# 2228_Emetteur_Alimentation.net
KiCad netlist of a schematic drawn in Altium Designer
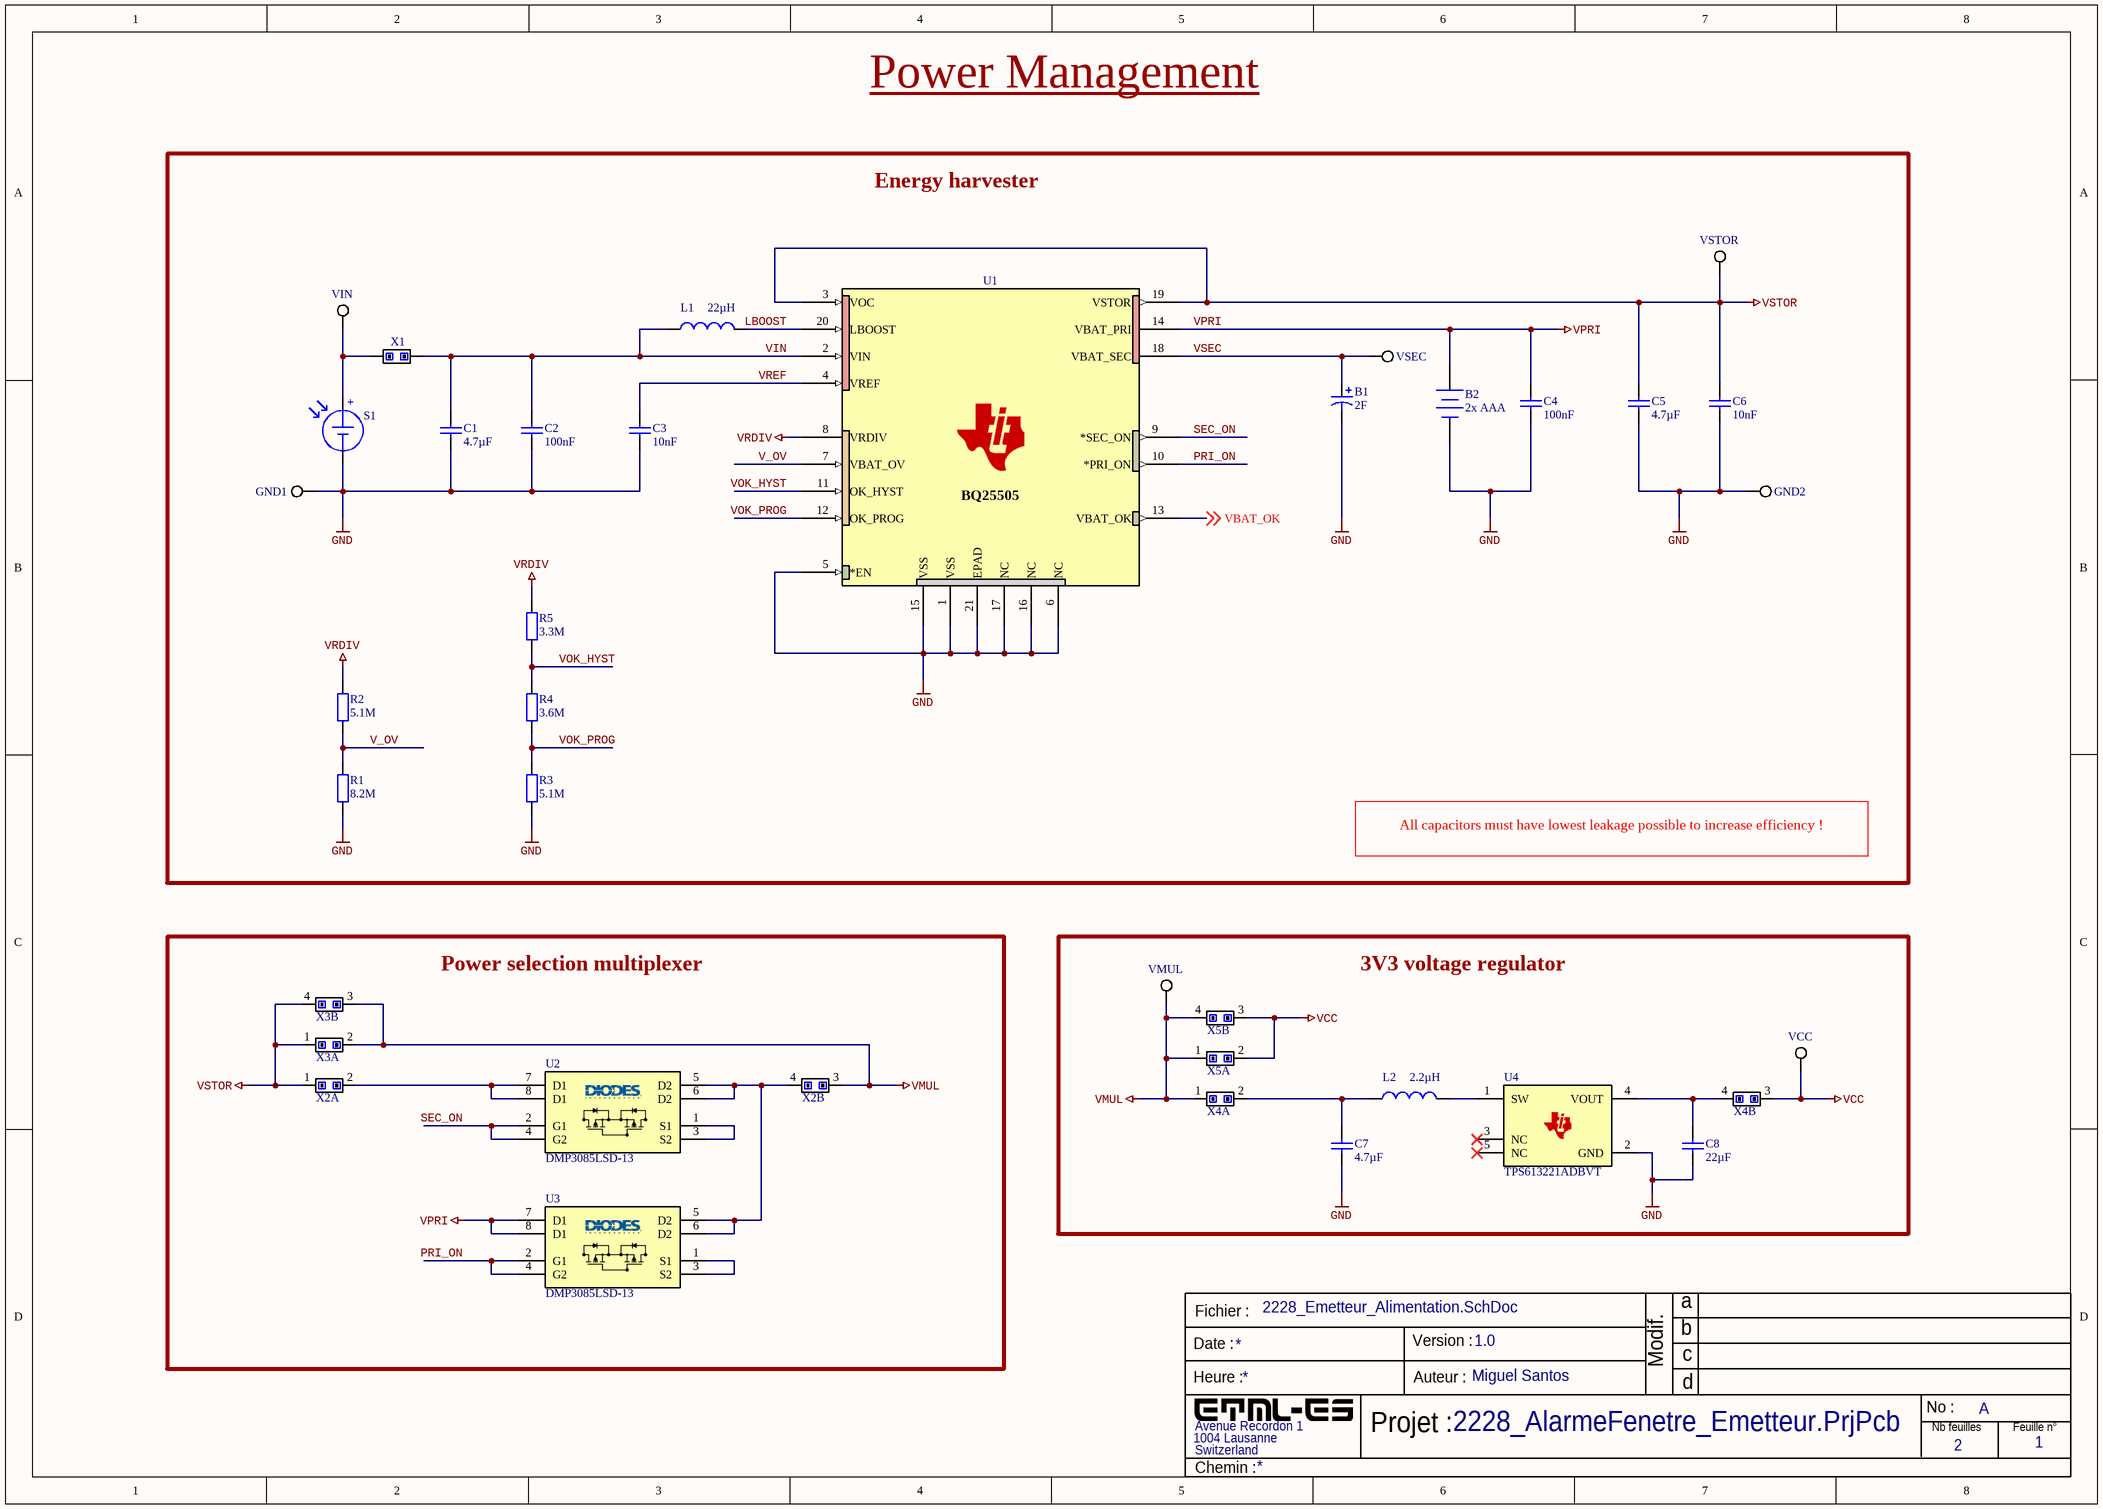
[diagram p0: 2228_Emetteur_Alimentation.SchDoc]

(export (version "E")
  (design (tool "Eeschema 10.0.6"))
  (components
    (comp (ref "B1")
      (value "2F")
      (footprint "2228_AlarmeFenetre_Footprints:SuperCap")
      (description "Polarized SuperCapacitor (Radial)")
      (fields (field (name "Comment") "SUPERCAP"))
      (libsource (lib "2228_AlarmeFenetre_Symbols") (part "SUPERCAP"))
    )
    (comp (ref "B2")
      (value "2x AAA")
      (footprint "WE_2PINS")
      (description "Multicell Battery")
      (libsource (lib "2228_AlarmeFenetre_Symbols") (part "Battery"))
    )
    (comp (ref "C1")
      (value "4.7µF")
      (footprint "CAP_0805")
      (description "Capacitor")
      (fields (field (name "Comment") "CAP_SMD"))
      (libsource (lib "2228_AlarmeFenetre_Symbols") (part "CAP_SMD"))
    )
    (comp (ref "C2")
      (value "100nF")
      (footprint "CAP_0805")
      (description "Capacitor")
      (fields (field (name "Comment") "CAP_SMD"))
      (libsource (lib "2228_AlarmeFenetre_Symbols") (part "CAP_SMD"))
    )
    (comp (ref "C3")
      (value "10nF")
      (footprint "CAP_0805")
      (description "Capacitor")
      (fields (field (name "Comment") "CAP_SMD"))
      (libsource (lib "2228_AlarmeFenetre_Symbols") (part "CAP_SMD"))
    )
    (comp (ref "C4")
      (value "100nF")
      (footprint "CAP_0805")
      (description "Capacitor")
      (fields (field (name "Comment") "CAP_SMD"))
      (libsource (lib "2228_AlarmeFenetre_Symbols") (part "CAP_SMD"))
    )
    (comp (ref "C5")
      (value "4.7µF")
      (footprint "CAP_0805")
      (description "Capacitor")
      (fields (field (name "Comment") "CAP_SMD"))
      (libsource (lib "2228_AlarmeFenetre_Symbols") (part "CAP_SMD"))
    )
    (comp (ref "C6")
      (value "10nF")
      (footprint "CAP_0805")
      (description "Capacitor")
      (fields (field (name "Comment") "CAP_SMD"))
      (libsource (lib "2228_AlarmeFenetre_Symbols") (part "CAP_SMD"))
    )
    (comp (ref "C7")
      (value "4.7µF")
      (footprint "CAP_0805")
      (description "Capacitor")
      (fields (field (name "Comment") "CAP_SMD"))
      (libsource (lib "2228_AlarmeFenetre_Symbols") (part "CAP_SMD"))
    )
    (comp (ref "C8")
      (value "22µF")
      (footprint "CAP_0805")
      (description "Capacitor")
      (fields (field (name "Comment") "CAP_SMD"))
      (libsource (lib "2228_AlarmeFenetre_Symbols") (part "CAP_SMD"))
    )
    (comp (ref "GND1")
      (value "5019")
      (footprint "KSTN-5019_V")
      (description "Test Point, 1 Position SMD, RoHS, Tape and Reel")
      (libsource (lib "Altium Content Vault") (part "TESTPOINT_WHITE"))
    )
    (comp (ref "GND2")
      (value "5019")
      (footprint "KSTN-5019_V")
      (description "Test Point, 1 Position SMD, RoHS, Tape and Reel")
      (libsource (lib "Altium Content Vault") (part "TESTPOINT_WHITE"))
    )
    (comp (ref "L1")
      (value "22µH")
      (footprint "WE-LQFS_4828")
      (description "Inductor SMD")
      (fields (field (name "Comment") "IND_SMD"))
      (libsource (lib "2228_AlarmeFenetre_Symbols") (part "IND_SMD"))
    )
    (comp (ref "L2")
      (value "2.2µH")
      (footprint "IND_0805")
      (description "Inductor SMD")
      (fields (field (name "Comment") "IND_SMD"))
      (libsource (lib "2228_AlarmeFenetre_Symbols") (part "IND_SMD"))
    )
    (comp (ref "R1")
      (value "8.2M")
      (footprint "RES_0805")
      (fields (field (name "Comment") "RES_SMD"))
      (libsource (lib "2228_AlarmeFenetre_Symbols") (part "RES_SMD"))
    )
    (comp (ref "R2")
      (value "5.1M")
      (footprint "RES_0805")
      (fields (field (name "Comment") "RES_SMD"))
      (libsource (lib "2228_AlarmeFenetre_Symbols") (part "RES_SMD"))
    )
    (comp (ref "R3")
      (value "5.1M")
      (footprint "RES_0805")
      (fields (field (name "Comment") "RES_SMD"))
      (libsource (lib "2228_AlarmeFenetre_Symbols") (part "RES_SMD"))
    )
    (comp (ref "R4")
      (value "3.6M")
      (footprint "RES_0805")
      (fields (field (name "Comment") "RES_SMD"))
      (libsource (lib "2228_AlarmeFenetre_Symbols") (part "RES_SMD"))
    )
    (comp (ref "R5")
      (value "3.3M")
      (footprint "RES_0805")
      (fields (field (name "Comment") "RES_SMD"))
      (libsource (lib "2228_AlarmeFenetre_Symbols") (part "RES_SMD"))
    )
    (comp (ref "S1")
      (value "Solar_Cell")
      (footprint "KXOB25-05X3F-TR")
      (description "Anysolar KXOB25-05X3F")
      (fields (field (name "MANUFACTURER") "Anysolar"))
      (libsource (lib "2228_AlarmeFenetre_Symbols") (part "Solar_Cell"))
    )
    (comp (ref "U1")
      (value "BQ25505")
      (footprint "2228_AlarmeFenetre_Footprints:QFN_25505")
      (description "Low power energy harvester")
      (fields (field (name "MANUFACTURER") "Texas Instruments"))
      (libsource (lib "2228_AlarmeFenetre_Symbols") (part "BQ25505RGRR"))
    )
    (comp (ref "U2")
      (value "DMP3085LSD-13")
      (footprint "2228_AlarmeFenetre_Footprints:SO-8")
      (fields (field (name "MANUFACTURER") "Diodes Inc"))
      (libsource (lib "2228_AlarmeFenetre_Symbols") (part "DMP3085LSD-13"))
    )
    (comp (ref "U3")
      (value "DMP3085LSD-13")
      (footprint "2228_AlarmeFenetre_Footprints:SO-8")
      (fields (field (name "MANUFACTURER") "Diodes Inc"))
      (libsource (lib "2228_AlarmeFenetre_Symbols") (part "DMP3085LSD-13"))
    )
    (comp (ref "U4")
      (value "TPS613221ADBVT")
      (footprint "2228_AlarmeFenetre_Footprints:SOT95P280X145-5N")
      (fields (field (name "MANUFACTURER") "Texas Instruments"))
      (libsource (lib "2228_AlarmeFenetre_Symbols") (part "TPS613221ADBVT"))
    )
    (comp (ref "VCC")
      (value "5019")
      (footprint "KSTN-5019_V")
      (description "Test Point, 1 Position SMD, RoHS, Tape and Reel")
      (libsource (lib "Altium Content Vault") (part "TESTPOINT_WHITE"))
    )
    (comp (ref "VIN")
      (value "5019")
      (footprint "KSTN-5019_V")
      (description "Test Point, 1 Position SMD, RoHS, Tape and Reel")
      (libsource (lib "Altium Content Vault") (part "TESTPOINT_WHITE"))
    )
    (comp (ref "VMUL")
      (value "5019")
      (footprint "KSTN-5019_V")
      (description "Test Point, 1 Position SMD, RoHS, Tape and Reel")
      (libsource (lib "Altium Content Vault") (part "TESTPOINT_WHITE"))
    )
    (comp (ref "VSEC")
      (value "5019")
      (footprint "KSTN-5019_V")
      (description "Test Point, 1 Position SMD, RoHS, Tape and Reel")
      (libsource (lib "Altium Content Vault") (part "TESTPOINT_WHITE"))
    )
    (comp (ref "VSTOR")
      (value "5019")
      (footprint "KSTN-5019_V")
      (description "Test Point, 1 Position SMD, RoHS, Tape and Reel")
      (libsource (lib "Altium Content Vault") (part "TESTPOINT_WHITE"))
    )
    (comp (ref "X1")
      (value "2PIN_HEADER")
      (footprint "HEADER_2PINS")
      (libsource (lib "2228_AlarmeFenetre_Symbols") (part "2PIN_HEADER"))
    )
    (comp (ref "X2")
      (value "2X2PIN_HEADER")
      (footprint "2x2_HEADER")
      (libsource (lib "2228_AlarmeFenetre_Symbols") (part "2X2PIN_HEADER"))
    )
    (comp (ref "X3")
      (value "2X2PIN_HEADER")
      (footprint "2x2_HEADER")
      (libsource (lib "") (part "2X2PIN_HEADER_1"))
    )
    (comp (ref "X4")
      (value "2X2PIN_HEADER")
      (footprint "2x2_HEADER")
      (libsource (lib "") (part "2X2PIN_HEADER_1"))
    )
    (comp (ref "X5")
      (value "2X2PIN_HEADER")
      (footprint "2x2_HEADER")
      (libsource (lib "") (part "2X2PIN_HEADER_1"))
    )
  )
  (nets
    (net (code "1") (name "/LBOOST") (class "Default")
      (node (ref "L1") (pin "2") (pinfunction "2_2") (pintype "passive"))
      (node (ref "U1") (pin "20") (pinfunction "LBOOST_20") (pintype "input"))
    )
    (net (code "2") (name "/PRI_ON") (class "Default")
      (node (ref "U1") (pin "10") (pinfunction "*PRI_ON_10") (pintype "output"))
      (node (ref "U3") (pin "2") (pinfunction "G1_2") (pintype "passive"))
      (node (ref "U3") (pin "4") (pinfunction "G2_4") (pintype "passive"))
    )
    (net (code "3") (name "/SEC_ON") (class "Default")
      (node (ref "U1") (pin "9") (pinfunction "*SEC_ON_9") (pintype "output"))
      (node (ref "U2") (pin "2") (pinfunction "G1_2") (pintype "passive"))
      (node (ref "U2") (pin "4") (pinfunction "G2_4") (pintype "passive"))
    )
    (net (code "4") (name "/VIN") (class "Default")
      (node (ref "C1") (pin "2") (pinfunction "2_2") (pintype "passive"))
      (node (ref "C2") (pin "2") (pinfunction "2_2") (pintype "passive"))
      (node (ref "L1") (pin "1") (pinfunction "1_1") (pintype "passive"))
      (node (ref "U1") (pin "2") (pinfunction "VIN_2") (pintype "input"))
      (node (ref "X1") (pin "2") (pinfunction "2_2") (pintype "passive"))
    )
    (net (code "5") (name "/VOK_HYST") (class "Default")
      (node (ref "R4") (pin "1") (pinfunction "1_1") (pintype "passive"))
      (node (ref "R5") (pin "2") (pinfunction "2_2") (pintype "passive"))
      (node (ref "U1") (pin "11") (pinfunction "OK_HYST_11") (pintype "input"))
    )
    (net (code "6") (name "/VOK_PROG") (class "Default")
      (node (ref "R3") (pin "1") (pinfunction "1_1") (pintype "passive"))
      (node (ref "R4") (pin "2") (pinfunction "2_2") (pintype "passive"))
      (node (ref "U1") (pin "12") (pinfunction "OK_PROG_12") (pintype "input"))
    )
    (net (code "7") (name "/VREF") (class "Default")
      (node (ref "C3") (pin "1") (pinfunction "1_1") (pintype "passive"))
      (node (ref "U1") (pin "4") (pinfunction "VREF_4") (pintype "input"))
    )
    (net (code "8") (name "/VSEC") (class "Default")
      (node (ref "B1") (pin "1") (pinfunction "1_1") (pintype "passive"))
      (node (ref "U1") (pin "18") (pinfunction "VBAT_SEC_18") (pintype "power_in"))
      (node (ref "VSEC") (pin "1") (pinfunction "1_1") (pintype "passive"))
    )
    (net (code "9") (name "/V_OV") (class "Default")
      (node (ref "R1") (pin "1") (pinfunction "1_1") (pintype "passive"))
      (node (ref "R2") (pin "2") (pinfunction "2_2") (pintype "passive"))
      (node (ref "U1") (pin "7") (pinfunction "VBAT_OV_7") (pintype "input"))
    )
    (net (code "10") (name "GND") (class "Default")
      (node (ref "B1") (pin "2") (pinfunction "2_2") (pintype "passive"))
      (node (ref "B2") (pin "2") (pinfunction "2_2") (pintype "passive"))
      (node (ref "C1") (pin "1") (pinfunction "1_1") (pintype "passive"))
      (node (ref "C2") (pin "1") (pinfunction "1_1") (pintype "passive"))
      (node (ref "C3") (pin "2") (pinfunction "2_2") (pintype "passive"))
      (node (ref "C4") (pin "1") (pinfunction "1_1") (pintype "passive"))
      (node (ref "C5") (pin "1") (pinfunction "1_1") (pintype "passive"))
      (node (ref "C6") (pin "1") (pinfunction "1_1") (pintype "passive"))
      (node (ref "C7") (pin "1") (pinfunction "1_1") (pintype "passive"))
      (node (ref "C8") (pin "1") (pinfunction "1_1") (pintype "passive"))
      (node (ref "GND1") (pin "1") (pinfunction "1_1") (pintype "passive"))
      (node (ref "GND2") (pin "1") (pinfunction "1_1") (pintype "passive"))
      (node (ref "R1") (pin "2") (pinfunction "2_2") (pintype "passive"))
      (node (ref "R3") (pin "2") (pinfunction "2_2") (pintype "passive"))
      (node (ref "S1") (pin "2") (pinfunction "-_2") (pintype "power_in"))
      (node (ref "U1") (pin "1") (pinfunction "VSS_1") (pintype "power_in"))
      (node (ref "U1") (pin "15") (pinfunction "VSS_15") (pintype "power_in"))
      (node (ref "U1") (pin "16") (pinfunction "NC_16") (pintype "passive"))
      (node (ref "U1") (pin "17") (pinfunction "NC_17") (pintype "passive"))
      (node (ref "U1") (pin "21") (pinfunction "EPAD_21") (pintype "passive"))
      (node (ref "U1") (pin "5") (pinfunction "*EN_5") (pintype "input"))
      (node (ref "U1") (pin "6") (pinfunction "NC_6") (pintype "passive"))
      (node (ref "U4") (pin "2") (pinfunction "GND_2") (pintype "power_in"))
    )
    (net (code "11") (name "Net-(C7-Pad2)") (class "Default")
      (node (ref "C7") (pin "2") (pinfunction "2_2") (pintype "passive"))
      (node (ref "L2") (pin "1") (pinfunction "1_1") (pintype "passive"))
      (node (ref "X4") (pin "2") (pinfunction "2_2") (pintype "passive"))
    )
    (net (code "12") (name "Net-(S1-+)") (class "Default")
      (node (ref "S1") (pin "1") (pinfunction "+_1") (pintype "power_in"))
      (node (ref "VIN") (pin "1") (pinfunction "1_1") (pintype "passive"))
      (node (ref "X1") (pin "1") (pinfunction "1_1") (pintype "passive"))
    )
    (net (code "13") (name "Net-(U2-D1-Pad7)") (class "Default")
      (node (ref "U2") (pin "7") (pinfunction "D1_7") (pintype "passive"))
      (node (ref "U2") (pin "8") (pinfunction "D1_8") (pintype "passive"))
      (node (ref "X2") (pin "2") (pinfunction "2_2") (pintype "passive"))
    )
    (net (code "14") (name "Net-(U2-D2-Pad5)") (class "Default")
      (node (ref "U2") (pin "5") (pinfunction "D2_5") (pintype "passive"))
      (node (ref "U2") (pin "6") (pinfunction "D2_6") (pintype "passive"))
      (node (ref "U3") (pin "5") (pinfunction "D2_5") (pintype "passive"))
      (node (ref "U3") (pin "6") (pinfunction "D2_6") (pintype "passive"))
      (node (ref "X2") (pin "4") (pinfunction "4_4") (pintype "passive"))
    )
    (net (code "15") (name "Net-(U2-S1)") (class "Default")
      (node (ref "U2") (pin "1") (pinfunction "S1_1") (pintype "passive"))
      (node (ref "U2") (pin "3") (pinfunction "S2_3") (pintype "passive"))
    )
    (net (code "16") (name "Net-(U3-S1)") (class "Default")
      (node (ref "U3") (pin "1") (pinfunction "S1_1") (pintype "passive"))
      (node (ref "U3") (pin "3") (pinfunction "S2_3") (pintype "passive"))
    )
    (net (code "17") (name "Net-(U4-SW)") (class "Default")
      (node (ref "L2") (pin "2") (pinfunction "2_2") (pintype "passive"))
      (node (ref "U4") (pin "1") (pinfunction "SW_1") (pintype "power_in"))
    )
    (net (code "18") (name "Net-(U4-VOUT)") (class "Default")
      (node (ref "C8") (pin "2") (pinfunction "2_2") (pintype "passive"))
      (node (ref "U4") (pin "4") (pinfunction "VOUT_4") (pintype "power_in"))
      (node (ref "X4") (pin "4") (pinfunction "4_4") (pintype "passive"))
    )
    (net (code "19") (name "VBAT_OK") (class "Default")
      (node (ref "U1") (pin "13") (pinfunction "VBAT_OK_13") (pintype "output"))
    )
    (net (code "20") (name "VCC") (class "Default")
      (node (ref "VCC") (pin "1") (pinfunction "1_1") (pintype "passive"))
      (node (ref "X4") (pin "3") (pinfunction "3_3") (pintype "passive"))
      (node (ref "X5") (pin "2") (pinfunction "2_2") (pintype "passive"))
      (node (ref "X5") (pin "3") (pinfunction "3_3") (pintype "passive"))
    )
    (net (code "21") (name "VMUL") (class "Default")
      (node (ref "VMUL") (pin "1") (pinfunction "1_1") (pintype "passive"))
      (node (ref "X2") (pin "3") (pinfunction "3_3") (pintype "passive"))
      (node (ref "X3") (pin "2") (pinfunction "2_2") (pintype "passive"))
      (node (ref "X3") (pin "3") (pinfunction "3_3") (pintype "passive"))
      (node (ref "X4") (pin "1") (pinfunction "1_1") (pintype "passive"))
      (node (ref "X5") (pin "1") (pinfunction "1_1") (pintype "passive"))
      (node (ref "X5") (pin "4") (pinfunction "4_4") (pintype "passive"))
    )
    (net (code "22") (name "VPRI") (class "Default")
      (node (ref "B2") (pin "1") (pinfunction "1_1") (pintype "passive"))
      (node (ref "C4") (pin "2") (pinfunction "2_2") (pintype "passive"))
      (node (ref "U1") (pin "14") (pinfunction "VBAT_PRI_14") (pintype "power_in"))
      (node (ref "U3") (pin "7") (pinfunction "D1_7") (pintype "passive"))
      (node (ref "U3") (pin "8") (pinfunction "D1_8") (pintype "passive"))
    )
    (net (code "23") (name "VRDIV") (class "Default")
      (node (ref "R2") (pin "1") (pinfunction "1_1") (pintype "passive"))
      (node (ref "R5") (pin "1") (pinfunction "1_1") (pintype "passive"))
      (node (ref "U1") (pin "8") (pinfunction "VRDIV_8") (pintype "power_in"))
    )
    (net (code "24") (name "VSTOR") (class "Default")
      (node (ref "C5") (pin "2") (pinfunction "2_2") (pintype "passive"))
      (node (ref "C6") (pin "2") (pinfunction "2_2") (pintype "passive"))
      (node (ref "U1") (pin "19") (pinfunction "VSTOR_19") (pintype "output"))
      (node (ref "U1") (pin "3") (pinfunction "VOC_3") (pintype "input"))
      (node (ref "VSTOR") (pin "1") (pinfunction "1_1") (pintype "passive"))
      (node (ref "X2") (pin "1") (pinfunction "1_1") (pintype "passive"))
      (node (ref "X3") (pin "1") (pinfunction "1_1") (pintype "passive"))
      (node (ref "X3") (pin "4") (pinfunction "4_4") (pintype "passive"))
    )
    (net (code "25") (name "unconnected-(U4-NC-Pad3)") (class "Default")
      (node (ref "U4") (pin "3") (pinfunction "NC_3") (pintype "passive+no_connect"))
    )
    (net (code "26") (name "unconnected-(U4-NC-Pad5)") (class "Default")
      (node (ref "U4") (pin "5") (pinfunction "NC_5") (pintype "passive+no_connect"))
    )
  )
)
